# LVDS_IFCA.net
KiCad netlist of a schematic drawn in Altium Designer
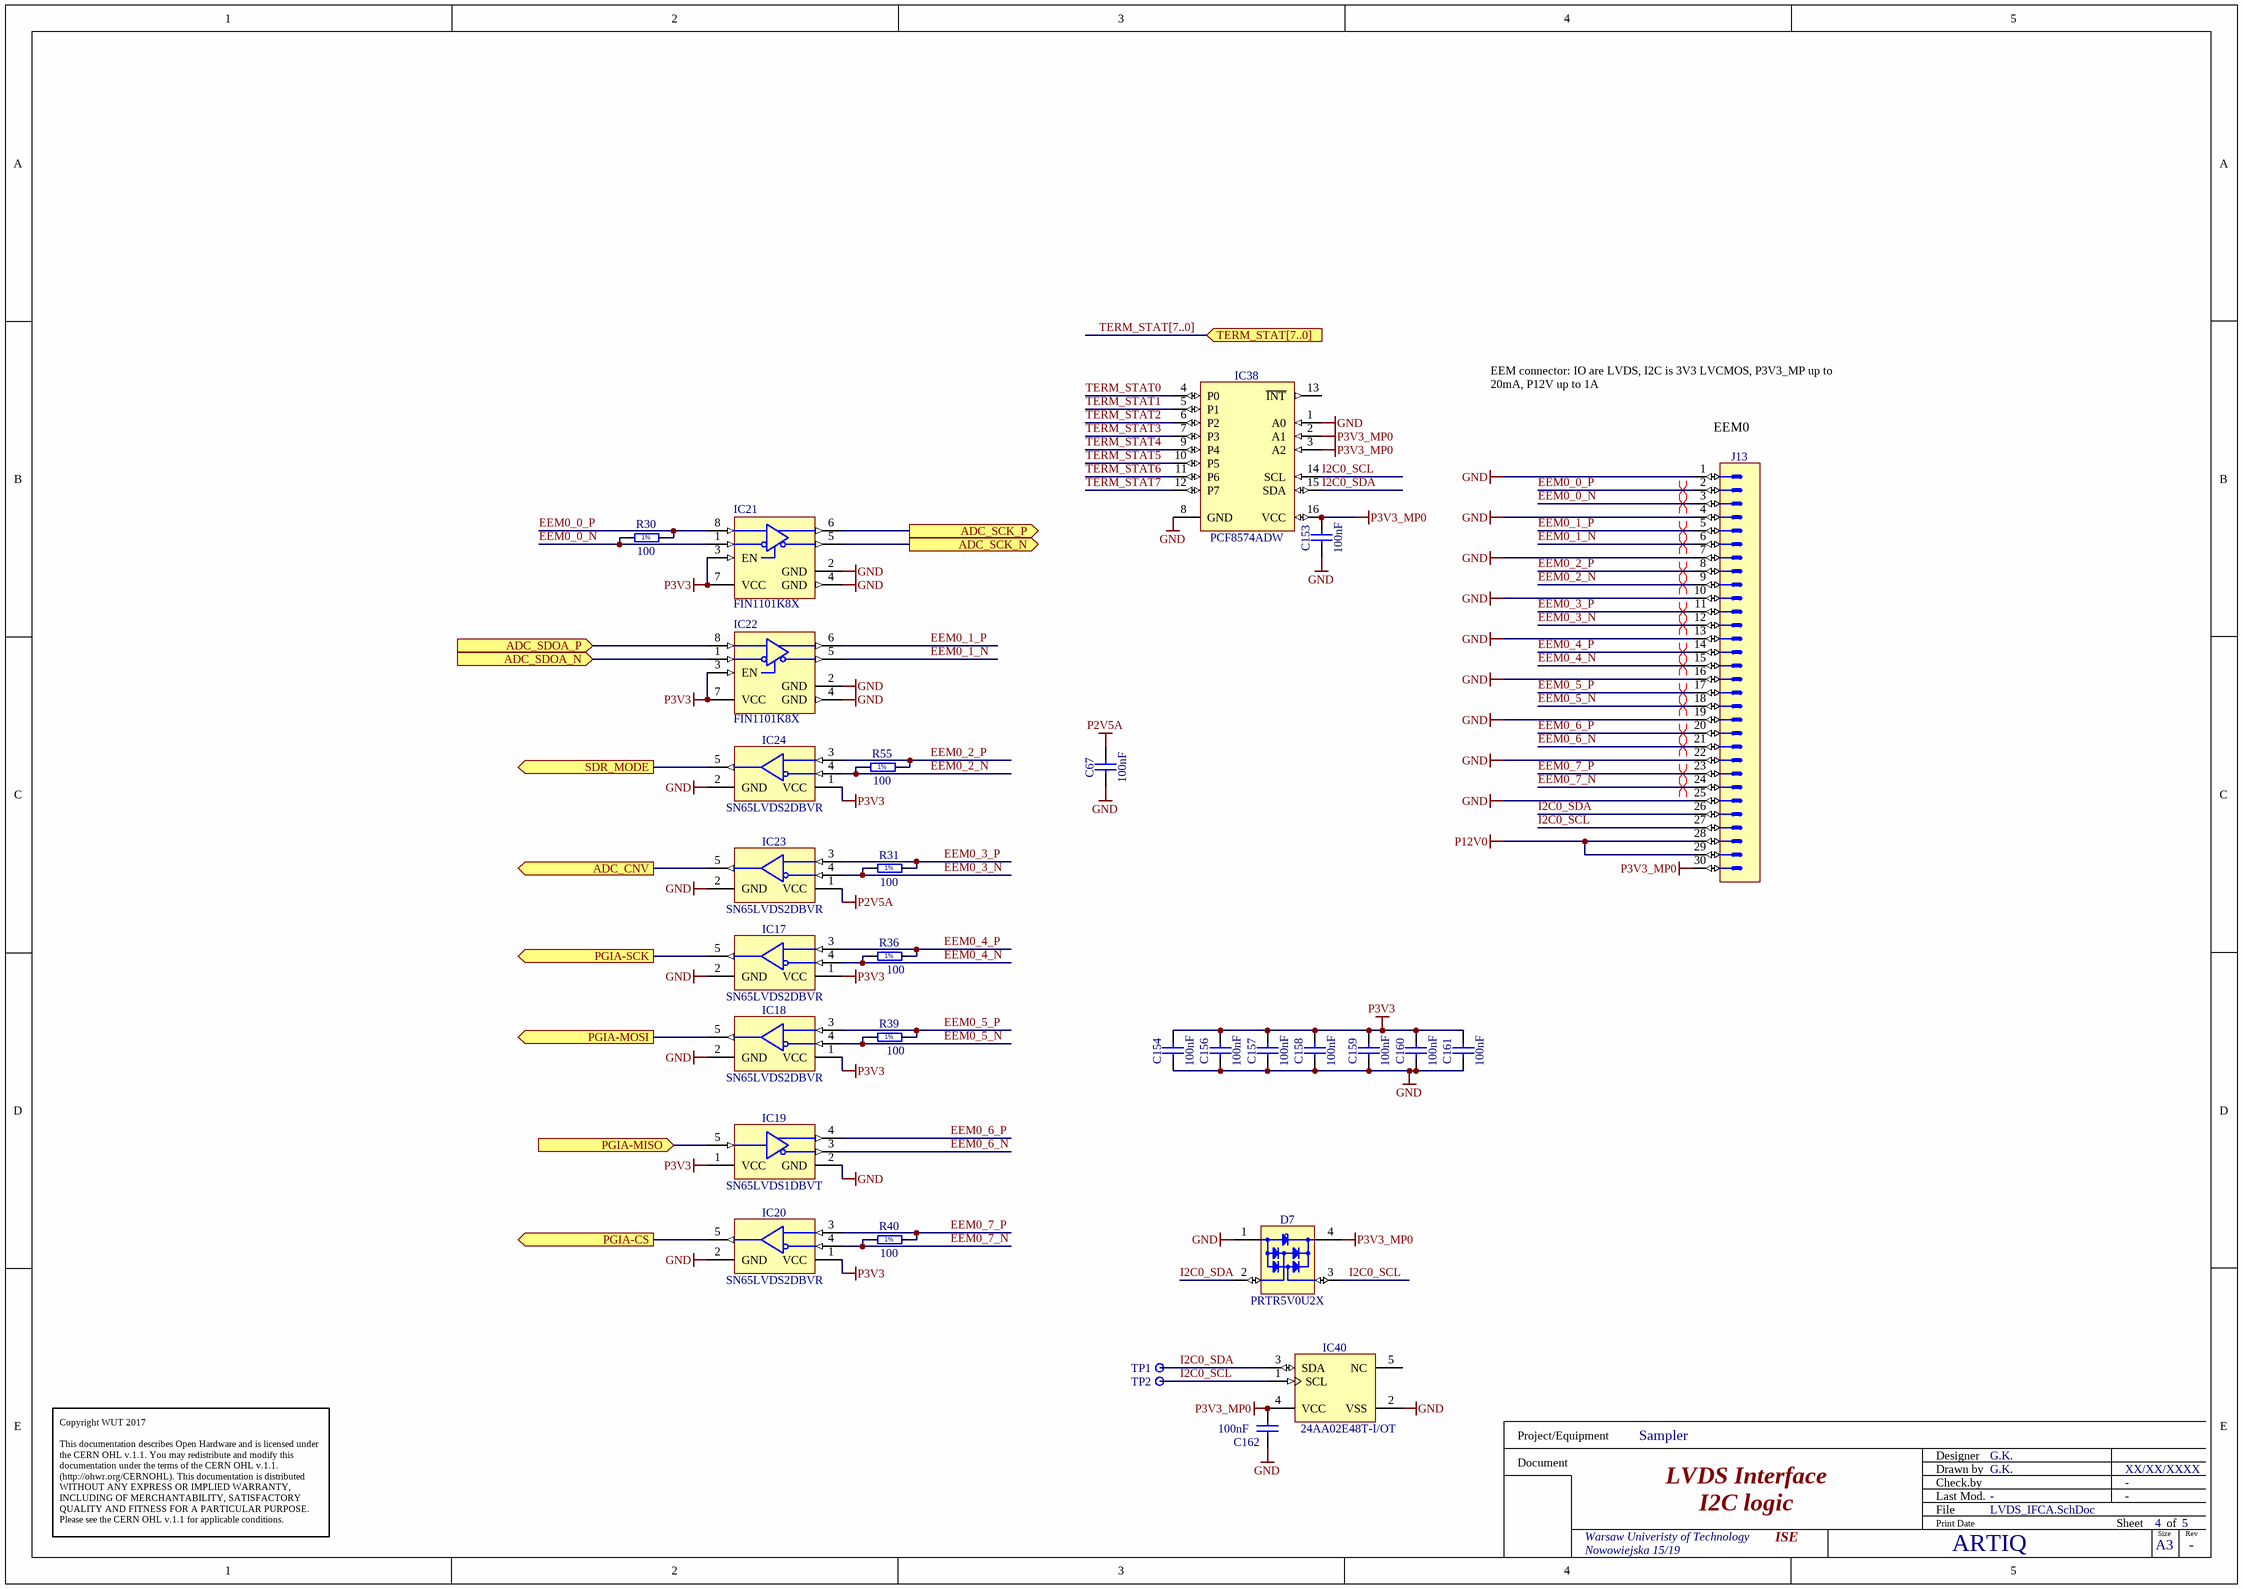
[diagram p0: LVDS_IFCA.SchDoc]

(export (version "E")
  (design (tool "Eeschema 10.0.6"))
  (components
    (comp (ref "C67")
      (value "100nF")
      (footprint "CAPC1005X55N")
      (description "Non-polarised capacitor")
      (fields
        (field (name "PART NUMBER") "CC0402_100NF_16V_10%_X5R")
        (field (name "VOLTAGE") "16V")
        (field (name "AUTHOR") "CERN DEM JLC")
      )
      (libsource (lib "Capacitors") (part "Capacitor - non polarized"))
    )
    (comp (ref "C153")
      (value "100nF")
      (footprint "CAPC1005X55N")
      (description "Non-polarised capacitor")
      (fields
        (field (name "PART NUMBER") "CC0402_100NF_16V_10%_X5R")
        (field (name "VOLTAGE") "16V")
        (field (name "AUTHOR") "CERN DEM JLC")
      )
      (libsource (lib "Capacitors") (part "Capacitor - non polarized"))
    )
    (comp (ref "C154")
      (value "100nF")
      (footprint "CAPC1005X55N")
      (description "Non-polarised capacitor")
      (fields
        (field (name "PART NUMBER") "CC0402_100NF_16V_10%_X5R")
        (field (name "VOLTAGE") "16V")
        (field (name "AUTHOR") "CERN DEM JLC")
      )
      (libsource (lib "Capacitors") (part "Capacitor - non polarized"))
    )
    (comp (ref "C156")
      (value "100nF")
      (footprint "CAPC1005X55N")
      (description "Non-polarised capacitor")
      (fields
        (field (name "PART NUMBER") "CC0402_100NF_16V_10%_X5R")
        (field (name "VOLTAGE") "16V")
        (field (name "AUTHOR") "CERN DEM JLC")
      )
      (libsource (lib "Capacitors") (part "Capacitor - non polarized"))
    )
    (comp (ref "C157")
      (value "100nF")
      (footprint "CAPC1005X55N")
      (description "Non-polarised capacitor")
      (fields
        (field (name "PART NUMBER") "CC0402_100NF_16V_10%_X5R")
        (field (name "VOLTAGE") "16V")
        (field (name "AUTHOR") "CERN DEM JLC")
      )
      (libsource (lib "Capacitors") (part "Capacitor - non polarized"))
    )
    (comp (ref "C158")
      (value "100nF")
      (footprint "CAPC1005X55N")
      (description "Non-polarised capacitor")
      (fields
        (field (name "PART NUMBER") "CC0402_100NF_16V_10%_X5R")
        (field (name "VOLTAGE") "16V")
        (field (name "AUTHOR") "CERN DEM JLC")
      )
      (libsource (lib "Capacitors") (part "Capacitor - non polarized"))
    )
    (comp (ref "C159")
      (value "100nF")
      (footprint "CAPC1005X55N")
      (description "Non-polarised capacitor")
      (fields
        (field (name "PART NUMBER") "CC0402_100NF_16V_10%_X5R")
        (field (name "VOLTAGE") "16V")
        (field (name "AUTHOR") "CERN DEM JLC")
      )
      (libsource (lib "Capacitors") (part "Capacitor - non polarized"))
    )
    (comp (ref "C160")
      (value "100nF")
      (footprint "CAPC1005X55N")
      (description "Non-polarised capacitor")
      (fields
        (field (name "PART NUMBER") "CC0402_100NF_16V_10%_X5R")
        (field (name "VOLTAGE") "16V")
        (field (name "AUTHOR") "CERN DEM JLC")
      )
      (libsource (lib "Capacitors") (part "Capacitor - non polarized"))
    )
    (comp (ref "C161")
      (value "100nF")
      (footprint "CAPC1005X55N")
      (description "Non-polarised capacitor")
      (fields
        (field (name "PART NUMBER") "CC0402_100NF_16V_10%_X5R")
        (field (name "VOLTAGE") "16V")
        (field (name "AUTHOR") "CERN DEM JLC")
      )
      (libsource (lib "Capacitors") (part "Capacitor - non polarized"))
    )
    (comp (ref "C162")
      (value "100nF")
      (footprint "CAPC1005X55N")
      (description "Non-polarised capacitor")
      (fields
        (field (name "PART NUMBER") "CC0402_100NF_16V_10%_X5R")
        (field (name "VOLTAGE") "16V")
        (field (name "AUTHOR") "CERN DEM JLC")
      )
      (libsource (lib "Capacitors") (part "Capacitor - non polarized"))
    )
    (comp (ref "D7")
      (value "PRTR5V0U2X")
      (footprint "SOT190P230X110-4N")
      (description "Ultra Low Capacitance Double Rail-to-Rail ESD Protection Diode")
      (fields
        (field (name "VOLTAGE") "5.5V")
        (field (name "MANUFACTURER") "NXP SEMICONDUCTORS")
        (field (name "AUTHOR") "CERN DEM JLC")
      )
      (libsource (lib "ICs And Semiconductors") (part "PRTR5V0U2X"))
    )
    (comp (ref "IC17")
      (value "SN65LVDS2DBVR")
      (footprint "SOT95P280X145-5N")
      (description "High-Speed Differential Line Receiver")
      (fields (field (name "MANUFACTURER") "TEXAS INSTRUMENTS") (field (name "AUTHOR") "CERN DEM JLC"))
      (libsource (lib "ICs And Semiconductors") (part "SN65LVDS2DBV"))
    )
    (comp (ref "IC18")
      (value "SN65LVDS2DBVR")
      (footprint "SOT95P280X145-5N")
      (description "High-Speed Differential Line Receiver")
      (fields (field (name "MANUFACTURER") "TEXAS INSTRUMENTS") (field (name "AUTHOR") "CERN DEM JLC"))
      (libsource (lib "ICs And Semiconductors") (part "SN65LVDS2DBV"))
    )
    (comp (ref "IC19")
      (value "SN65LVDS1DBVT")
      (footprint "SOT95P280X145-5N")
      (description "High-Speed Differential Line Driver")
      (fields (field (name "MANUFACTURER") "TEXAS INSTRUMENTS") (field (name "AUTHOR") "CERN DEM JLC"))
      (libsource (lib "ICs And Semiconductors") (part "SN65LVDS1DBV"))
    )
    (comp (ref "IC20")
      (value "SN65LVDS2DBVR")
      (footprint "SOT95P280X145-5N")
      (description "High-Speed Differential Line Receiver")
      (fields (field (name "MANUFACTURER") "TEXAS INSTRUMENTS") (field (name "AUTHOR") "CERN DEM JLC"))
      (libsource (lib "ICs And Semiconductors") (part "SN65LVDS2DBV"))
    )
    (comp (ref "IC21")
      (value "FIN1101K8X")
      (footprint "SOP50P310X90-8N")
      (description "LVDS Single Port High Speed Repeater")
      (fields (field (name "MANUFACTURER") "FAIRCHILD SEMICONDUCTOR") (field (name "AUTHOR") "CERN DEM JLC"))
      (libsource (lib "ICs And Semiconductors") (part "FIN1101K8X"))
    )
    (comp (ref "IC22")
      (value "FIN1101K8X")
      (footprint "SOP50P310X90-8N")
      (description "LVDS Single Port High Speed Repeater")
      (fields (field (name "MANUFACTURER") "FAIRCHILD SEMICONDUCTOR") (field (name "AUTHOR") "CERN DEM JLC"))
      (libsource (lib "ICs And Semiconductors") (part "FIN1101K8X"))
    )
    (comp (ref "IC23")
      (value "SN65LVDS2DBVR")
      (footprint "SOT95P280X145-5N")
      (description "High-Speed Differential Line Receiver")
      (fields (field (name "MANUFACTURER") "TEXAS INSTRUMENTS") (field (name "AUTHOR") "CERN DEM JLC"))
      (libsource (lib "ICs And Semiconductors") (part "SN65LVDS2DBV"))
    )
    (comp (ref "IC24")
      (value "SN65LVDS2DBVR")
      (footprint "SOT95P280X145-5N")
      (description "High-Speed Differential Line Receiver")
      (fields (field (name "MANUFACTURER") "TEXAS INSTRUMENTS") (field (name "AUTHOR") "CERN DEM JLC"))
      (libsource (lib "ICs And Semiconductors") (part "SN65LVDS2DBV"))
    )
    (comp (ref "IC38")
      (value "PCF8574ADW")
      (footprint "SOIC127P1030X265-16N")
      (description "Remote 8-bit I/O Expander For I2C Bus")
      (fields (field (name "MANUFACTURER") "TEXAS INSTRUMENTS") (field (name "AUTHOR") "CERN DEM JLC"))
      (libsource (lib "ICs And Semiconductors") (part "PCF8574ADW"))
    )
    (comp (ref "IC40")
      (value "24AA02E48T-I/OT")
      (footprint "SOT95P280X145-5N")
      (description "1.7V-5.5V, 2K I2C Serial EEPROM With EUI-48 Node Identity")
      (fields (field (name "MANUFACTURER") "MICROCHIP TECHNOLOGY") (field (name "AUTHOR") "CERN DEM MR"))
      (libsource (lib "ICs And Semiconductors") (part "24AA02E48T-I/OT"))
    )
    (comp (ref "J13")
      (value "~")
      (footprint "3M_N2530-6002RB")
      (description "Connector 30 Male")
      (fields
        (field (name "PART NUMBER") "3M_N2530-6002RB")
        (field (name "MANUFACTURER") "3M")
        (field (name "AUTHOR") "CERN DEM JLC")
      )
      (libsource (lib "Connectors") (part "Connector 30 Male"))
    )
    (comp (ref "R30")
      (value "100")
      (footprint "RESC1005X40N")
      (description "Resistor - 1%")
      (fields
        (field (name "PART NUMBER") "R0402_100R_1%_0.1W_100PPM")
        (field (name "POWER") "0.1W")
        (field (name "AUTHOR") "CERN DEM JLC")
      )
      (libsource (lib "Resistors") (part "Resistor - 1%"))
    )
    (comp (ref "R31")
      (value "100")
      (footprint "RESC1005X40N")
      (description "Resistor - 1%")
      (fields
        (field (name "PART NUMBER") "R0402_100R_1%_0.1W_100PPM")
        (field (name "POWER") "0.1W")
        (field (name "AUTHOR") "CERN DEM JLC")
      )
      (libsource (lib "Resistors") (part "Resistor - 1%"))
    )
    (comp (ref "R36")
      (value "100")
      (footprint "RESC1005X40N")
      (description "Resistor - 1%")
      (fields
        (field (name "PART NUMBER") "R0402_100R_1%_0.1W_100PPM")
        (field (name "POWER") "0.1W")
        (field (name "AUTHOR") "CERN DEM JLC")
      )
      (libsource (lib "Resistors") (part "Resistor - 1%"))
    )
    (comp (ref "R39")
      (value "100")
      (footprint "RESC1005X40N")
      (description "Resistor - 1%")
      (fields
        (field (name "PART NUMBER") "R0402_100R_1%_0.1W_100PPM")
        (field (name "POWER") "0.1W")
        (field (name "AUTHOR") "CERN DEM JLC")
      )
      (libsource (lib "Resistors") (part "Resistor - 1%"))
    )
    (comp (ref "R40")
      (value "100")
      (footprint "RESC1005X40N")
      (description "Resistor - 1%")
      (fields
        (field (name "PART NUMBER") "R0402_100R_1%_0.1W_100PPM")
        (field (name "POWER") "0.1W")
        (field (name "AUTHOR") "CERN DEM JLC")
      )
      (libsource (lib "Resistors") (part "Resistor - 1%"))
    )
    (comp (ref "R55")
      (value "100")
      (footprint "RESC1005X40N")
      (description "Resistor - 1%")
      (fields
        (field (name "PART NUMBER") "R0402_100R_1%_0.1W_100PPM")
        (field (name "POWER") "0.1W")
        (field (name "AUTHOR") "CERN DEM JLC")
      )
      (libsource (lib "Resistors") (part "Resistor - 1%"))
    )
    (comp (ref "TP1")
      (value "Test Point")
      (footprint "TPS127")
      (fields (field (name "PART NUMBER") "SMD_PAD_1.27X1.27MM") (field (name "AUTHOR") "CERN DEM JLC"))
      (libsource (lib "Eletro-mechanical") (part "Test Point"))
    )
    (comp (ref "TP2")
      (value "Test Point")
      (footprint "TPS127")
      (fields (field (name "PART NUMBER") "SMD_PAD_1.27X1.27MM") (field (name "AUTHOR") "CERN DEM JLC"))
      (libsource (lib "Eletro-mechanical") (part "Test Point"))
    )
  )
  (nets
    (net (code "1") (name "/ADC_CNV") (class "Default")
      (node (ref "IC23") (pin "5") (pinfunction "R_5") (pintype "output"))
    )
    (net (code "2") (name "/ADC_SCK_N") (class "Default")
      (node (ref "IC21") (pin "5") (pinfunction "DOUT-_5") (pintype "output"))
    )
    (net (code "3") (name "/ADC_SCK_P") (class "Default")
      (node (ref "IC21") (pin "6") (pinfunction "DOUT+_6") (pintype "output"))
    )
    (net (code "4") (name "/ADC_SDOA_N") (class "Default")
      (node (ref "IC22") (pin "1") (pinfunction "RIN-_1") (pintype "input"))
    )
    (net (code "5") (name "/ADC_SDOA_P") (class "Default")
      (node (ref "IC22") (pin "8") (pinfunction "RIN+_8") (pintype "input"))
    )
    (net (code "6") (name "/EEM0_0_N") (class "Default")
      (node (ref "IC21") (pin "1") (pinfunction "RIN-_1") (pintype "input"))
      (node (ref "J13") (pin "3") (pinfunction "3_3") (pintype "bidirectional"))
      (node (ref "R30") (pin "1") (pinfunction "1_1") (pintype "passive"))
    )
    (net (code "7") (name "/EEM0_0_P") (class "Default")
      (node (ref "IC21") (pin "8") (pinfunction "RIN+_8") (pintype "input"))
      (node (ref "J13") (pin "2") (pinfunction "2_2") (pintype "bidirectional"))
      (node (ref "R30") (pin "2") (pinfunction "2_2") (pintype "passive"))
    )
    (net (code "8") (name "/EEM0_1_N") (class "Default")
      (node (ref "IC22") (pin "5") (pinfunction "DOUT-_5") (pintype "output"))
      (node (ref "J13") (pin "6") (pinfunction "6_6") (pintype "bidirectional"))
    )
    (net (code "9") (name "/EEM0_1_P") (class "Default")
      (node (ref "IC22") (pin "6") (pinfunction "DOUT+_6") (pintype "output"))
      (node (ref "J13") (pin "5") (pinfunction "5_5") (pintype "bidirectional"))
    )
    (net (code "10") (name "/EEM0_2_N") (class "Default")
      (node (ref "IC24") (pin "4") (pinfunction "B_4") (pintype "input"))
      (node (ref "J13") (pin "9") (pinfunction "9_9") (pintype "bidirectional"))
      (node (ref "R55") (pin "1") (pinfunction "1_1") (pintype "passive"))
    )
    (net (code "11") (name "/EEM0_2_P") (class "Default")
      (node (ref "IC24") (pin "3") (pinfunction "A_3") (pintype "input"))
      (node (ref "J13") (pin "8") (pinfunction "8_8") (pintype "bidirectional"))
      (node (ref "R55") (pin "2") (pinfunction "2_2") (pintype "passive"))
    )
    (net (code "12") (name "/EEM0_3_N") (class "Default")
      (node (ref "IC23") (pin "4") (pinfunction "B_4") (pintype "input"))
      (node (ref "J13") (pin "12") (pinfunction "12_12") (pintype "bidirectional"))
      (node (ref "R31") (pin "1") (pinfunction "1_1") (pintype "passive"))
    )
    (net (code "13") (name "/EEM0_3_P") (class "Default")
      (node (ref "IC23") (pin "3") (pinfunction "A_3") (pintype "input"))
      (node (ref "J13") (pin "11") (pinfunction "11_11") (pintype "bidirectional"))
      (node (ref "R31") (pin "2") (pinfunction "2_2") (pintype "passive"))
    )
    (net (code "14") (name "/EEM0_4_N") (class "Default")
      (node (ref "IC17") (pin "4") (pinfunction "B_4") (pintype "input"))
      (node (ref "J13") (pin "15") (pinfunction "15_15") (pintype "bidirectional"))
      (node (ref "R36") (pin "1") (pinfunction "1_1") (pintype "passive"))
    )
    (net (code "15") (name "/EEM0_4_P") (class "Default")
      (node (ref "IC17") (pin "3") (pinfunction "A_3") (pintype "input"))
      (node (ref "J13") (pin "14") (pinfunction "14_14") (pintype "bidirectional"))
      (node (ref "R36") (pin "2") (pinfunction "2_2") (pintype "passive"))
    )
    (net (code "16") (name "/EEM0_5_N") (class "Default")
      (node (ref "IC18") (pin "4") (pinfunction "B_4") (pintype "input"))
      (node (ref "J13") (pin "18") (pinfunction "18_18") (pintype "bidirectional"))
      (node (ref "R39") (pin "1") (pinfunction "1_1") (pintype "passive"))
    )
    (net (code "17") (name "/EEM0_5_P") (class "Default")
      (node (ref "IC18") (pin "3") (pinfunction "A_3") (pintype "input"))
      (node (ref "J13") (pin "17") (pinfunction "17_17") (pintype "bidirectional"))
      (node (ref "R39") (pin "2") (pinfunction "2_2") (pintype "passive"))
    )
    (net (code "18") (name "/EEM0_6_N") (class "Default")
      (node (ref "IC19") (pin "3") (pinfunction "A_3") (pintype "output"))
      (node (ref "J13") (pin "21") (pinfunction "21_21") (pintype "bidirectional"))
    )
    (net (code "19") (name "/EEM0_6_P") (class "Default")
      (node (ref "IC19") (pin "4") (pinfunction "B_4") (pintype "output"))
      (node (ref "J13") (pin "20") (pinfunction "20_20") (pintype "bidirectional"))
    )
    (net (code "20") (name "/EEM0_7_N") (class "Default")
      (node (ref "IC20") (pin "4") (pinfunction "B_4") (pintype "input"))
      (node (ref "J13") (pin "24") (pinfunction "24_24") (pintype "bidirectional"))
      (node (ref "R40") (pin "1") (pinfunction "1_1") (pintype "passive"))
    )
    (net (code "21") (name "/EEM0_7_P") (class "Default")
      (node (ref "IC20") (pin "3") (pinfunction "A_3") (pintype "input"))
      (node (ref "J13") (pin "23") (pinfunction "23_23") (pintype "bidirectional"))
      (node (ref "R40") (pin "2") (pinfunction "2_2") (pintype "passive"))
    )
    (net (code "22") (name "/I2C0_SCL") (class "Default")
      (node (ref "D7") (pin "3") (pinfunction "I/O2_3") (pintype "bidirectional"))
      (node (ref "IC38") (pin "14") (pinfunction "SCL_14") (pintype "input"))
      (node (ref "IC40") (pin "1") (pinfunction "SCL_1") (pintype "input"))
      (node (ref "J13") (pin "27") (pinfunction "27_27") (pintype "bidirectional"))
      (node (ref "TP2") (pin "1") (pinfunction "1_1") (pintype "bidirectional"))
    )
    (net (code "23") (name "/I2C0_SDA") (class "Default")
      (node (ref "D7") (pin "2") (pinfunction "I/O1_2") (pintype "bidirectional"))
      (node (ref "IC38") (pin "15") (pinfunction "SDA_15") (pintype "bidirectional"))
      (node (ref "IC40") (pin "3") (pinfunction "SDA_3") (pintype "bidirectional"))
      (node (ref "J13") (pin "26") (pinfunction "26_26") (pintype "bidirectional"))
      (node (ref "TP1") (pin "1") (pinfunction "1_1") (pintype "bidirectional"))
    )
    (net (code "24") (name "/PGIA-CS") (class "Default")
      (node (ref "IC20") (pin "5") (pinfunction "R_5") (pintype "output"))
    )
    (net (code "25") (name "/PGIA-MISO") (class "Default")
      (node (ref "IC19") (pin "5") (pinfunction "R_5") (pintype "input"))
    )
    (net (code "26") (name "/PGIA-MOSI") (class "Default")
      (node (ref "IC18") (pin "5") (pinfunction "R_5") (pintype "output"))
    )
    (net (code "27") (name "/PGIA-SCK") (class "Default")
      (node (ref "IC17") (pin "5") (pinfunction "R_5") (pintype "output"))
    )
    (net (code "28") (name "/SDR_MODE") (class "Default")
      (node (ref "IC24") (pin "5") (pinfunction "R_5") (pintype "output"))
    )
    (net (code "29") (name "/TERM_STAT0") (class "Default")
      (node (ref "IC38") (pin "4") (pinfunction "P0_4") (pintype "bidirectional"))
    )
    (net (code "30") (name "/TERM_STAT1") (class "Default")
      (node (ref "IC38") (pin "5") (pinfunction "P1_5") (pintype "bidirectional"))
    )
    (net (code "31") (name "/TERM_STAT2") (class "Default")
      (node (ref "IC38") (pin "6") (pinfunction "P2_6") (pintype "bidirectional"))
    )
    (net (code "32") (name "/TERM_STAT3") (class "Default")
      (node (ref "IC38") (pin "7") (pinfunction "P3_7") (pintype "bidirectional"))
    )
    (net (code "33") (name "/TERM_STAT4") (class "Default")
      (node (ref "IC38") (pin "9") (pinfunction "P4_9") (pintype "bidirectional"))
    )
    (net (code "34") (name "/TERM_STAT5") (class "Default")
      (node (ref "IC38") (pin "10") (pinfunction "P5_10") (pintype "bidirectional"))
    )
    (net (code "35") (name "/TERM_STAT6") (class "Default")
      (node (ref "IC38") (pin "11") (pinfunction "P6_11") (pintype "bidirectional"))
    )
    (net (code "36") (name "/TERM_STAT7") (class "Default")
      (node (ref "IC38") (pin "12") (pinfunction "P7_12") (pintype "bidirectional"))
    )
    (net (code "38") (name "GND") (class "Default")
      (node (ref "C153") (pin "1") (pinfunction "1_1") (pintype "passive"))
      (node (ref "C154") (pin "1") (pinfunction "1_1") (pintype "passive"))
      (node (ref "C156") (pin "1") (pinfunction "1_1") (pintype "passive"))
      (node (ref "C157") (pin "1") (pinfunction "1_1") (pintype "passive"))
      (node (ref "C158") (pin "1") (pinfunction "1_1") (pintype "passive"))
      (node (ref "C159") (pin "1") (pinfunction "1_1") (pintype "passive"))
      (node (ref "C160") (pin "1") (pinfunction "1_1") (pintype "passive"))
      (node (ref "C161") (pin "1") (pinfunction "1_1") (pintype "passive"))
      (node (ref "C162") (pin "1") (pinfunction "1_1") (pintype "passive"))
      (node (ref "C67") (pin "1") (pinfunction "1_1") (pintype "passive"))
      (node (ref "D7") (pin "1") (pinfunction "GND_1") (pintype "power_in"))
      (node (ref "IC17") (pin "2") (pinfunction "GND_2") (pintype "power_in"))
      (node (ref "IC18") (pin "2") (pinfunction "GND_2") (pintype "power_in"))
      (node (ref "IC19") (pin "2") (pinfunction "GND_2") (pintype "power_in"))
      (node (ref "IC20") (pin "2") (pinfunction "GND_2") (pintype "power_in"))
      (node (ref "IC21") (pin "2") (pinfunction "GND_2") (pintype "power_in"))
      (node (ref "IC21") (pin "4") (pinfunction "GND_4") (pintype "output"))
      (node (ref "IC22") (pin "2") (pinfunction "GND_2") (pintype "power_in"))
      (node (ref "IC22") (pin "4") (pinfunction "GND_4") (pintype "output"))
      (node (ref "IC23") (pin "2") (pinfunction "GND_2") (pintype "power_in"))
      (node (ref "IC24") (pin "2") (pinfunction "GND_2") (pintype "power_in"))
      (node (ref "IC38") (pin "1") (pinfunction "A0_1") (pintype "input"))
      (node (ref "IC38") (pin "8") (pinfunction "GND_8") (pintype "power_in"))
      (node (ref "IC40") (pin "2") (pinfunction "VSS_2") (pintype "power_in"))
      (node (ref "J13") (pin "1") (pinfunction "1_1") (pintype "bidirectional"))
      (node (ref "J13") (pin "10") (pinfunction "10_10") (pintype "bidirectional"))
      (node (ref "J13") (pin "13") (pinfunction "13_13") (pintype "bidirectional"))
      (node (ref "J13") (pin "16") (pinfunction "16_16") (pintype "bidirectional"))
      (node (ref "J13") (pin "19") (pinfunction "19_19") (pintype "bidirectional"))
      (node (ref "J13") (pin "22") (pinfunction "22_22") (pintype "bidirectional"))
      (node (ref "J13") (pin "25") (pinfunction "25_25") (pintype "bidirectional"))
      (node (ref "J13") (pin "4") (pinfunction "4_4") (pintype "bidirectional"))
      (node (ref "J13") (pin "7") (pinfunction "7_7") (pintype "bidirectional"))
    )
    (net (code "39") (name "P2V5A") (class "Default")
      (node (ref "C67") (pin "2") (pinfunction "2_2") (pintype "passive"))
      (node (ref "IC23") (pin "1") (pinfunction "VCC_1") (pintype "power_in"))
    )
    (net (code "40") (name "P3V3") (class "Default")
      (node (ref "C154") (pin "2") (pinfunction "2_2") (pintype "passive"))
      (node (ref "C156") (pin "2") (pinfunction "2_2") (pintype "passive"))
      (node (ref "C157") (pin "2") (pinfunction "2_2") (pintype "passive"))
      (node (ref "C158") (pin "2") (pinfunction "2_2") (pintype "passive"))
      (node (ref "C159") (pin "2") (pinfunction "2_2") (pintype "passive"))
      (node (ref "C160") (pin "2") (pinfunction "2_2") (pintype "passive"))
      (node (ref "C161") (pin "2") (pinfunction "2_2") (pintype "passive"))
      (node (ref "IC17") (pin "1") (pinfunction "VCC_1") (pintype "power_in"))
      (node (ref "IC18") (pin "1") (pinfunction "VCC_1") (pintype "power_in"))
      (node (ref "IC19") (pin "1") (pinfunction "VCC_1") (pintype "power_in"))
      (node (ref "IC20") (pin "1") (pinfunction "VCC_1") (pintype "power_in"))
      (node (ref "IC21") (pin "3") (pinfunction "EN_3") (pintype "input"))
      (node (ref "IC21") (pin "7") (pinfunction "VCC_7") (pintype "power_in"))
      (node (ref "IC22") (pin "3") (pinfunction "EN_3") (pintype "input"))
      (node (ref "IC22") (pin "7") (pinfunction "VCC_7") (pintype "power_in"))
      (node (ref "IC24") (pin "1") (pinfunction "VCC_1") (pintype "power_in"))
    )
    (net (code "41") (name "P3V3_MP0") (class "Default")
      (node (ref "C153") (pin "2") (pinfunction "2_2") (pintype "passive"))
      (node (ref "C162") (pin "2") (pinfunction "2_2") (pintype "passive"))
      (node (ref "D7") (pin "4") (pinfunction "VCC_4") (pintype "power_in"))
      (node (ref "IC38") (pin "16") (pinfunction "VCC_16") (pintype "bidirectional"))
      (node (ref "IC38") (pin "2") (pinfunction "A1_2") (pintype "input"))
      (node (ref "IC38") (pin "3") (pinfunction "A2_3") (pintype "input"))
      (node (ref "IC40") (pin "4") (pinfunction "VCC_4") (pintype "power_in"))
      (node (ref "J13") (pin "30") (pinfunction "30_30") (pintype "bidirectional"))
    )
    (net (code "42") (name "P12V0") (class "Default")
      (node (ref "J13") (pin "28") (pinfunction "28_28") (pintype "bidirectional"))
      (node (ref "J13") (pin "29") (pinfunction "29_29") (pintype "bidirectional"))
    )
    (net (code "43") (name "unconnected-(IC38-~{INT}-Pad13)") (class "Default")
      (node (ref "IC38") (pin "13") (pinfunction "~{INT}_13") (pintype "output"))
    )
    (net (code "44") (name "unconnected-(IC40-NC-Pad5)") (class "Default")
      (node (ref "IC40") (pin "5") (pinfunction "NC_5") (pintype "passive"))
    )
  )
)
